# ProPrj_FOC_-L6234_2025-07-28.net
KiCad netlist of a schematic drawn in EasyEDA Pro
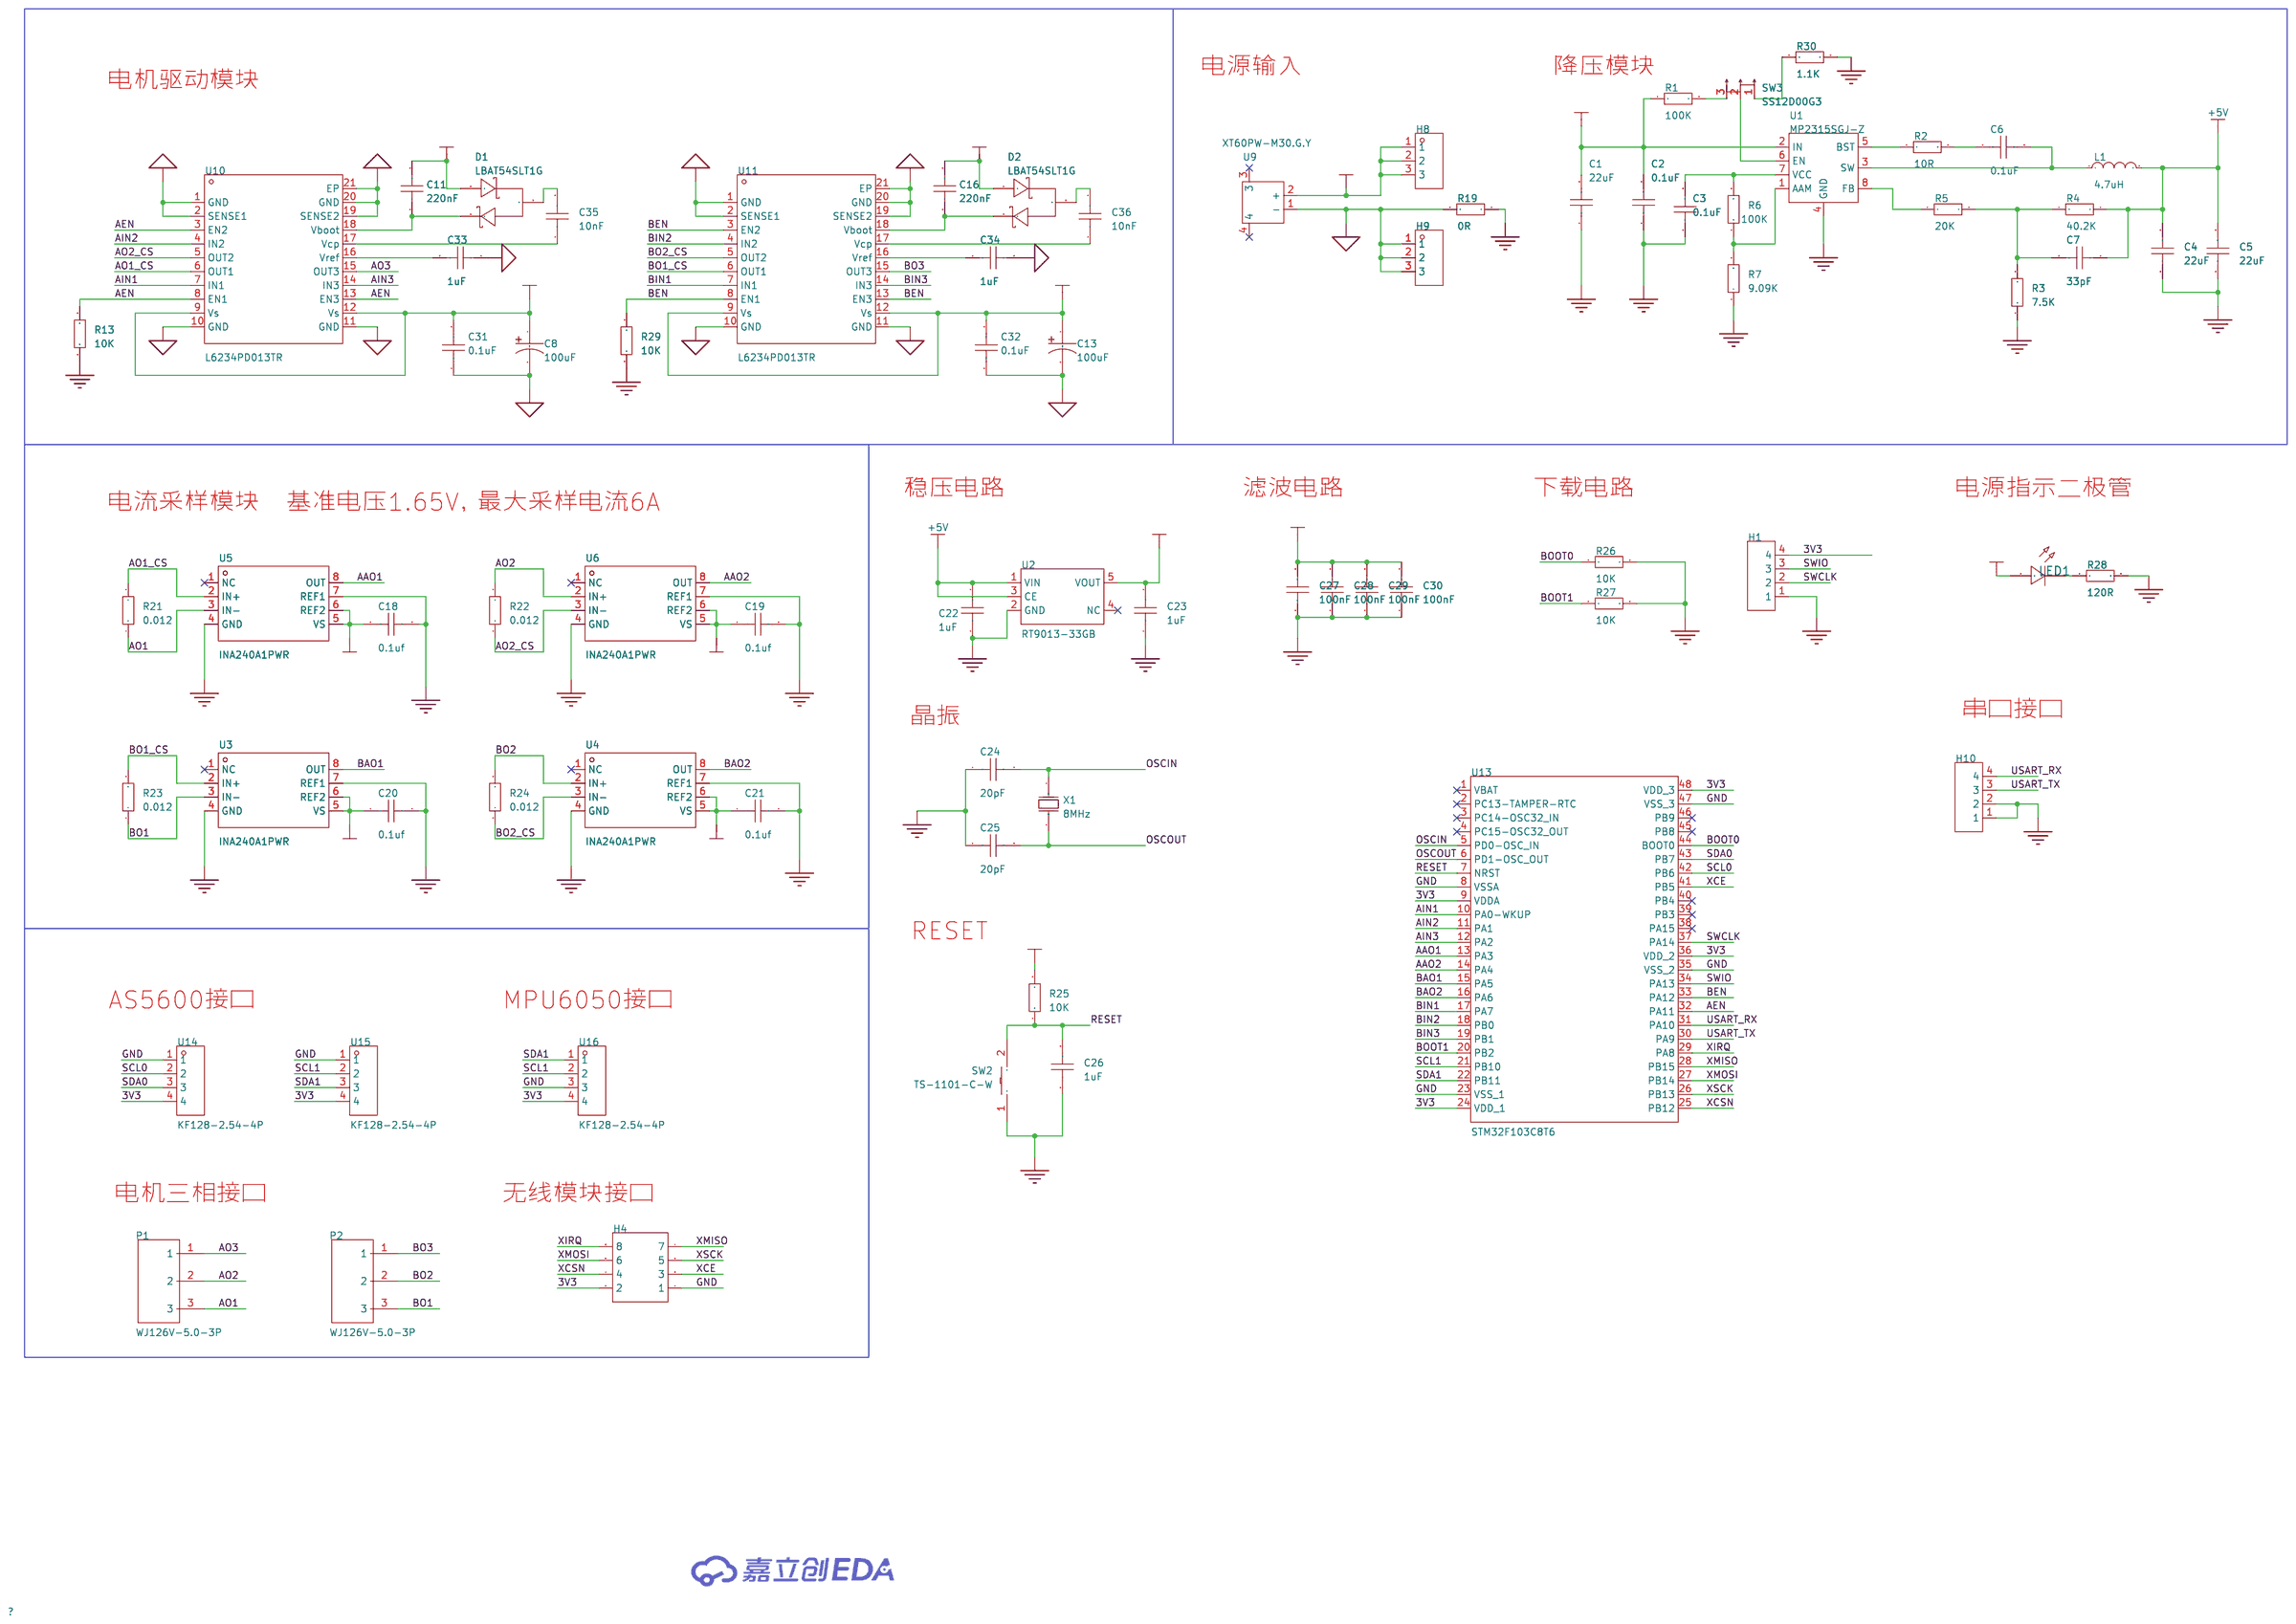
[diagram p0: schematic sheet]

(export (version "E")
  (design (tool "Eeschema 10.0.6"))
  (components
    (comp (ref "C1")
      (value "22uF")
      (footprint "easyedapro:C0603")
      (fields
        (field (name "Manufacturer Part") "CGA1206X5R226M350NT")
        (field (name "Manufacturer") "HRE(芯声)")
      )
      (libsource (lib "easyedapro") (part "CapAcitance"))
    )
    (comp (ref "C2")
      (value "0.1uF")
      (footprint "easyedapro:C0603")
      (libsource (lib "easyedapro") (part "CapAcitance"))
    )
    (comp (ref "C3")
      (value "0.1uF")
      (footprint "easyedapro:C0603")
      (libsource (lib "easyedapro") (part "CapAcitance"))
    )
    (comp (ref "C4")
      (value "22uF")
      (footprint "easyedapro:C0603")
      (fields
        (field (name "Manufacturer Part") "CGA0805X5R226M350MT")
        (field (name "Manufacturer") "HRE(芯声)")
      )
      (libsource (lib "easyedapro") (part "CapAcitance"))
    )
    (comp (ref "C5")
      (value "22uF")
      (footprint "easyedapro:C0603")
      (fields
        (field (name "Manufacturer Part") "CGA0805X5R226M350MT")
        (field (name "Manufacturer") "HRE(芯声)")
      )
      (libsource (lib "easyedapro") (part "CapAcitance"))
    )
    (comp (ref "C6")
      (value "0.1uF")
      (footprint "easyedapro:C0603")
      (libsource (lib "easyedapro") (part "CapAcitance"))
    )
    (comp (ref "C7")
      (value "33pF")
      (footprint "easyedapro:C0603")
      (libsource (lib "easyedapro") (part "CapAcitance"))
    )
    (comp (ref "C8")
      (value "100uF")
      (footprint "easyedapro:CAP-SMD_BD6.3-L6.6-W6.6-FD")
      (description "容值:100uF;精度:±20%;额定电压:35V;纹波电流:-;等效串联电阻:-;")
      (fields (field (name "Manufacturer Part") "RVE1V101M0607") (field (name "Manufacturer") "HONOR(荣誉)"))
      (libsource (lib "easyedapro") (part "RVE1V101M0607"))
    )
    (comp (ref "C11")
      (value "220nF")
      (footprint "easyedapro:C0603")
      (libsource (lib "easyedapro") (part "CapAcitance"))
    )
    (comp (ref "C13")
      (value "100uF")
      (footprint "easyedapro:CAP-SMD_BD6.3-L6.6-W6.6-FD")
      (description "容值:100uF;精度:±20%;额定电压:35V;纹波电流:-;等效串联电阻:-;")
      (fields (field (name "Manufacturer Part") "RVE1V101M0607") (field (name "Manufacturer") "HONOR(荣誉)"))
      (libsource (lib "easyedapro") (part "RVE1V101M0607"))
    )
    (comp (ref "C16")
      (value "220nF")
      (footprint "easyedapro:C0603")
      (libsource (lib "easyedapro") (part "CapAcitance"))
    )
    (comp (ref "C18")
      (value "0.1uf")
      (footprint "easyedapro:C0603")
      (libsource (lib "easyedapro") (part "CapAcitance"))
    )
    (comp (ref "C19")
      (value "0.1uf")
      (footprint "easyedapro:C0603")
      (libsource (lib "easyedapro") (part "CapAcitance"))
    )
    (comp (ref "C20")
      (value "0.1uf")
      (footprint "easyedapro:C0603")
      (libsource (lib "easyedapro") (part "CapAcitance"))
    )
    (comp (ref "C21")
      (value "0.1uf")
      (footprint "easyedapro:C0603")
      (libsource (lib "easyedapro") (part "CapAcitance"))
    )
    (comp (ref "C22")
      (value "1uF")
      (footprint "easyedapro:C0603")
      (libsource (lib "easyedapro") (part "CapAcitance"))
    )
    (comp (ref "C23")
      (value "1uF")
      (footprint "easyedapro:C0603")
      (libsource (lib "easyedapro") (part "CapAcitance"))
    )
    (comp (ref "C24")
      (value "20pF")
      (footprint "easyedapro:C0603")
      (libsource (lib "easyedapro") (part "CapAcitance"))
    )
    (comp (ref "C25")
      (value "20pF")
      (footprint "easyedapro:C0603")
      (libsource (lib "easyedapro") (part "CapAcitance"))
    )
    (comp (ref "C26")
      (value "1uF")
      (footprint "easyedapro:C0603")
      (libsource (lib "easyedapro") (part "CapAcitance"))
    )
    (comp (ref "C27")
      (value "100nF")
      (footprint "easyedapro:C0603")
      (libsource (lib "easyedapro") (part "CapAcitance"))
    )
    (comp (ref "C28")
      (value "100nF")
      (footprint "easyedapro:C0603")
      (libsource (lib "easyedapro") (part "CapAcitance"))
    )
    (comp (ref "C29")
      (value "100nF")
      (footprint "easyedapro:C0603")
      (libsource (lib "easyedapro") (part "CapAcitance"))
    )
    (comp (ref "C30")
      (value "100nF")
      (footprint "easyedapro:C0603")
      (libsource (lib "easyedapro") (part "CapAcitance"))
    )
    (comp (ref "C31")
      (value "0.1uF")
      (footprint "easyedapro:C0603")
      (libsource (lib "easyedapro") (part "CapAcitance"))
    )
    (comp (ref "C32")
      (value "0.1uF")
      (footprint "easyedapro:C0603")
      (libsource (lib "easyedapro") (part "CapAcitance"))
    )
    (comp (ref "C33")
      (value "1uF")
      (footprint "easyedapro:C0603")
      (libsource (lib "easyedapro") (part "CapAcitance"))
    )
    (comp (ref "C34")
      (value "1uF")
      (footprint "easyedapro:C0603")
      (libsource (lib "easyedapro") (part "CapAcitance"))
    )
    (comp (ref "C35")
      (value "10nF")
      (footprint "easyedapro:C0603")
      (libsource (lib "easyedapro") (part "CapAcitance"))
    )
    (comp (ref "C36")
      (value "10nF")
      (footprint "easyedapro:C0603")
      (libsource (lib "easyedapro") (part "CapAcitance"))
    )
    (comp (ref "D1")
      (value "LBAT54SLT1G")
      (footprint "easyedapro:SOT-23_L2.9-W1.3-P1.90-LS2.4-BR")
      (description "正向压降(Vf):400mV;直流反向耐压(Vr):30V;整流电流:200mA;")
      (fields (field (name "Manufacturer") "LRC(乐山无线电)"))
      (libsource (lib "easyedapro") (part "LBAT54SLT1G"))
    )
    (comp (ref "D2")
      (value "LBAT54SLT1G")
      (footprint "easyedapro:SOT-23_L2.9-W1.3-P1.90-LS2.4-BR")
      (description "正向压降(Vf):400mV;直流反向耐压(Vr):30V;整流电流:200mA;")
      (fields (field (name "Manufacturer") "LRC(乐山无线电)"))
      (libsource (lib "easyedapro") (part "LBAT54SLT1G"))
    )
    (comp (ref "H1")
      (value "~")
      (footprint "easyedapro:HDR-TH_4P-P2.54-V-M")
      (libsource (lib "easyedapro") (part "PZ254V-11-04P"))
    )
    (comp (ref "H4")
      (value "~")
      (footprint "easyedapro:HDR-TH_8P-P2.54-V-F-R2-C4-S2.54-1")
      (libsource (lib "easyedapro") (part "HDR-F-2.54_2x4"))
    )
    (comp (ref "H8")
      (value "~")
      (footprint "easyedapro:HDR-TH_3P-P2.54-V-M")
      (libsource (lib "easyedapro") (part "PZ254V-11-03P_C2937625"))
    )
    (comp (ref "H9")
      (value "~")
      (footprint "easyedapro:HDR-TH_3P-P2.54-V-M")
      (libsource (lib "easyedapro") (part "PZ254V-11-03P_C2937625"))
    )
    (comp (ref "H10")
      (value "~")
      (footprint "easyedapro:HDR-TH_4P-P2.54-V-M")
      (libsource (lib "easyedapro") (part "PZ254V-11-04P"))
    )
    (comp (ref "L1")
      (value "4.7uH")
      (footprint "easyedapro:IND-SMD_L7.3-W6.6")
      (description "电感值:4.7uH;精度:±20%;额定电流:5.5A;饱和电流(Isat):7A;")
      (fields (field (name "Manufacturer Part") "MCS0630-4R7MPY1") (field (name "Manufacturer") "PSA(信昌电陶)"))
      (libsource (lib "easyedapro") (part "MCS0630-4R7MPY1"))
    )
    (comp (ref "LED1")
      (value "~")
      (footprint "easyedapro:LED_0603")
      (libsource (lib "easyedapro") (part "LED_R"))
    )
    (comp (ref "P1")
      (value "WJ126V-5.0-3P")
      (footprint "easyedapro:CONN-TH_3P-P5.00_WJ126V-5.0-3P")
      (fields (field (name "Manufacturer") "KANGNEX(康奈克斯电气)"))
      (libsource (lib "easyedapro") (part "WJ126V-5.0-3P"))
    )
    (comp (ref "P2")
      (value "WJ126V-5.0-3P")
      (footprint "easyedapro:CONN-TH_3P-P5.00_WJ126V-5.0-3P")
      (fields (field (name "Manufacturer") "KANGNEX(康奈克斯电气)"))
      (libsource (lib "easyedapro") (part "WJ126V-5.0-3P"))
    )
    (comp (ref "R1") (value "100K") (footprint "easyedapro:R0805") (libsource (lib "easyedapro") (part "电阻")))
    (comp (ref "R2") (value "10R") (footprint "easyedapro:R0805") (libsource (lib "easyedapro") (part "电阻")))
    (comp (ref "R3") (value "7.5K") (footprint "easyedapro:R0805") (libsource (lib "easyedapro") (part "电阻")))
    (comp (ref "R4")
      (value "40.2K")
      (footprint "easyedapro:R0805")
      (libsource (lib "easyedapro") (part "电阻"))
    )
    (comp (ref "R5") (value "20K") (footprint "easyedapro:R0805") (libsource (lib "easyedapro") (part "电阻")))
    (comp (ref "R6") (value "100K") (footprint "easyedapro:R0805") (libsource (lib "easyedapro") (part "电阻")))
    (comp (ref "R7")
      (value "9.09K")
      (footprint "easyedapro:R0805")
      (libsource (lib "easyedapro") (part "电阻"))
    )
    (comp (ref "R13") (value "10K") (footprint "easyedapro:R0805") (libsource (lib "easyedapro") (part "电阻")))
    (comp (ref "R19") (value "0R") (footprint "easyedapro:R0805") (libsource (lib "easyedapro") (part "电阻")))
    (comp (ref "R21")
      (value "0.012")
      (footprint "easyedapro:R0805")
      (libsource (lib "easyedapro") (part "电阻"))
    )
    (comp (ref "R22")
      (value "0.012")
      (footprint "easyedapro:R0805")
      (libsource (lib "easyedapro") (part "电阻"))
    )
    (comp (ref "R23")
      (value "0.012")
      (footprint "easyedapro:R0805")
      (libsource (lib "easyedapro") (part "电阻"))
    )
    (comp (ref "R24")
      (value "0.012")
      (footprint "easyedapro:R0805")
      (libsource (lib "easyedapro") (part "电阻"))
    )
    (comp (ref "R25") (value "10K") (footprint "easyedapro:R0805") (libsource (lib "easyedapro") (part "电阻")))
    (comp (ref "R26") (value "10K") (footprint "easyedapro:R0805") (libsource (lib "easyedapro") (part "电阻")))
    (comp (ref "R27") (value "10K") (footprint "easyedapro:R0805") (libsource (lib "easyedapro") (part "电阻")))
    (comp (ref "R28")
      (value "120R")
      (footprint "easyedapro:R0805")
      (libsource (lib "easyedapro") (part "电阻"))
    )
    (comp (ref "R29") (value "10K") (footprint "easyedapro:R0805") (libsource (lib "easyedapro") (part "电阻")))
    (comp (ref "R30")
      (value "1.1K")
      (footprint "easyedapro:R0805")
      (libsource (lib "easyedapro") (part "电阻"))
    )
    (comp (ref "SW2")
      (value "TS-1101-C-W")
      (footprint "easyedapro:SW-SMD_L6.0-W3.3-LS8.0")
      (fields (field (name "Manufacturer") "XKB Connectivity(中国星坤)"))
      (libsource (lib "easyedapro") (part "TS-1101-C-W"))
    )
    (comp (ref "SW3")
      (value "SS12D00G3")
      (footprint "easyedapro:SW-TH_SS-12D01-GX")
      (libsource (lib "easyedapro") (part "SS12D00G3"))
    )
    (comp (ref "U1")
      (value "MP2315SGJ-Z")
      (footprint "easyedapro:TSOT-23-8_L2.9-W1.6-P0.65-LS2.8-BL")
      (description "功能类型:降压型;输出类型:固定;工作电压:4.5V~24V;输出电压:800mV~22.8V;输出电流:3A;")
      (fields (field (name "Manufacturer") "MPS(芯源)"))
      (libsource (lib "easyedapro") (part "MP2315SGJ-Z"))
    )
    (comp (ref "U2")
      (value "RT9013-33GB")
      (footprint "easyedapro:SOT-23-5_L2.9-W1.6-P0.95-LS2.8-BR")
      (description "输出类型:固定;工作电压:7V;输出电压:3.3V;输出电流:500mA;电源纹波抑制比(PSRR):-;输出极性:正极;")
      (fields (field (name "Manufacturer") "TECH PUBLIC(台舟)"))
      (libsource (lib "easyedapro") (part "RT9013-33GB_C19268157"))
    )
    (comp (ref "U3")
      (value "INA240A1PWR")
      (footprint "easyedapro:TSSOP-8_L4.4-W3.0-P0.65-LS6.4-BL")
      (description "放大器数:单路;")
      (fields (field (name "Manufacturer") "TI(德州仪器)"))
      (libsource (lib "easyedapro") (part "INA240A2PWR"))
    )
    (comp (ref "U4")
      (value "INA240A1PWR")
      (footprint "easyedapro:TSSOP-8_L4.4-W3.0-P0.65-LS6.4-BL")
      (description "放大器数:单路;")
      (fields (field (name "Manufacturer") "TI(德州仪器)"))
      (libsource (lib "easyedapro") (part "INA240A2PWR"))
    )
    (comp (ref "U5")
      (value "INA240A1PWR")
      (footprint "easyedapro:TSSOP-8_L4.4-W3.0-P0.65-LS6.4-BL")
      (description "放大器数:单路;")
      (fields (field (name "Manufacturer") "TI(德州仪器)"))
      (libsource (lib "easyedapro") (part "INA240A2PWR"))
    )
    (comp (ref "U6")
      (value "INA240A1PWR")
      (footprint "easyedapro:TSSOP-8_L4.4-W3.0-P0.65-LS6.4-BL")
      (description "放大器数:单路;")
      (fields (field (name "Manufacturer") "TI(德州仪器)"))
      (libsource (lib "easyedapro") (part "INA240A2PWR"))
    )
    (comp (ref "U9")
      (value "XT60PW-M30.G.Y")
      (footprint "easyedapro:CONN-TH_XT60PW-M")
      (libsource (lib "easyedapro") (part "XT60PW-M30.G.Y"))
    )
    (comp (ref "U10")
      (value "L6234PD013TR")
      (footprint "easyedapro:POWERSO20_L15.9-W11.0-P1.27-LS14.2-BL-EP")
      (description "三相电机驱动器")
      (fields (field (name "Manufacturer") "ST(意法半导体)"))
      (libsource (lib "easyedapro") (part "L6234PD013TR"))
    )
    (comp (ref "U11")
      (value "L6234PD013TR")
      (footprint "easyedapro:POWERSO20_L15.9-W11.0-P1.27-LS14.2-BL-EP")
      (description "三相电机驱动器")
      (fields (field (name "Manufacturer") "ST(意法半导体)"))
      (libsource (lib "easyedapro") (part "L6234PD013TR"))
    )
    (comp (ref "U13")
      (value "STM32F103C8T6")
      (footprint "easyedapro:LQFP-48_L7.0-W7.0-P0.50-LS9.0-BL")
      (description "CPU内核:ARM-M3;CPU最大主频:72MHz;应用领域:-;")
      (fields (field (name "Manufacturer") "ST(意法半导体)"))
      (libsource (lib "easyedapro") (part "STM32F103C8T6"))
    )
    (comp (ref "U14")
      (value "KF128-2.54-4P")
      (footprint "easyedapro:CONN-TH_4P-P2.54_KF128-2.54-4P")
      (fields (field (name "Manufacturer") "KEFA(科发)"))
      (libsource (lib "easyedapro") (part "KF128-2.54-4P"))
    )
    (comp (ref "U15")
      (value "KF128-2.54-4P")
      (footprint "easyedapro:CONN-TH_4P-P2.54_KF128-2.54-4P")
      (fields (field (name "Manufacturer") "KEFA(科发)"))
      (libsource (lib "easyedapro") (part "KF128-2.54-4P"))
    )
    (comp (ref "U16")
      (value "KF128-2.54-4P")
      (footprint "easyedapro:CONN-TH_4P-P2.54_KF128-2.54-4P")
      (fields (field (name "Manufacturer") "KEFA(科发)"))
      (libsource (lib "easyedapro") (part "KF128-2.54-4P"))
    )
    (comp (ref "X1")
      (value "8MHz")
      (fields (field (name "Manufacturer Part") "X49SD8MSD2SC") (field (name "Manufacturer") "YXC(扬兴晶振)"))
      (libsource (lib "easyedapro") (part "X49SM8MSD2SC"))
    )
  )
  (nets
    (net (code "1") (name "+5V") (class "Default")
      (node (ref "C22") (pin "2") (pinfunction "2_2") (pintype "input"))
      (node (ref "C4") (pin "2") (pinfunction "2_2") (pintype "input"))
      (node (ref "C5") (pin "2") (pinfunction "2_2") (pintype "input"))
      (node (ref "C7") (pin "2") (pinfunction "2_2") (pintype "input"))
      (node (ref "L1") (pin "2") (pinfunction "2_2") (pintype "unspecified"))
      (node (ref "R4") (pin "2") (pinfunction "2_2") (pintype "input"))
      (node (ref "U2") (pin "1") (pinfunction "VIN_1") (pintype "unspecified"))
      (node (ref "U2") (pin "3") (pinfunction "CE_3") (pintype "unspecified"))
    )
    (net (code "2") (name "/AAO1") (class "Default")
      (node (ref "U13") (pin "13") (pinfunction "PA3_13") (pintype "unspecified"))
      (node (ref "U5") (pin "8") (pinfunction "OUT_8") (pintype "unspecified"))
    )
    (net (code "3") (name "/AAO2") (class "Default")
      (node (ref "U13") (pin "14") (pinfunction "PA4_14") (pintype "unspecified"))
      (node (ref "U6") (pin "8") (pinfunction "OUT_8") (pintype "unspecified"))
    )
    (net (code "4") (name "/AEN") (class "Default")
      (node (ref "R13") (pin "2") (pinfunction "2_2") (pintype "input"))
      (node (ref "U10") (pin "13") (pinfunction "EN3_13") (pintype "unspecified"))
      (node (ref "U10") (pin "3") (pinfunction "EN2_3") (pintype "unspecified"))
      (node (ref "U10") (pin "8") (pinfunction "EN1_8") (pintype "unspecified"))
      (node (ref "U13") (pin "32") (pinfunction "PA11_32") (pintype "unspecified"))
    )
    (net (code "5") (name "/AIN1") (class "Default")
      (node (ref "U10") (pin "7") (pinfunction "IN1_7") (pintype "unspecified"))
      (node (ref "U13") (pin "10") (pinfunction "PA0-WKUP_10") (pintype "unspecified"))
    )
    (net (code "6") (name "/AIN2") (class "Default")
      (node (ref "U10") (pin "4") (pinfunction "IN2_4") (pintype "unspecified"))
      (node (ref "U13") (pin "11") (pinfunction "PA1_11") (pintype "unspecified"))
    )
    (net (code "7") (name "/AIN3") (class "Default")
      (node (ref "U10") (pin "14") (pinfunction "IN3_14") (pintype "unspecified"))
      (node (ref "U13") (pin "12") (pinfunction "PA2_12") (pintype "unspecified"))
    )
    (net (code "8") (name "/AO1") (class "Default")
      (node (ref "P1") (pin "3") (pinfunction "3_3") (pintype "input"))
      (node (ref "R21") (pin "1") (pinfunction "1_1") (pintype "input"))
      (node (ref "U5") (pin "3") (pinfunction "IN-_3") (pintype "unspecified"))
    )
    (net (code "9") (name "/AO1_CS") (class "Default")
      (node (ref "R21") (pin "2") (pinfunction "2_2") (pintype "input"))
      (node (ref "U10") (pin "6") (pinfunction "OUT1_6") (pintype "unspecified"))
      (node (ref "U5") (pin "2") (pinfunction "IN+_2") (pintype "unspecified"))
    )
    (net (code "10") (name "/AO2") (class "Default")
      (node (ref "P1") (pin "2") (pinfunction "2_2") (pintype "input"))
      (node (ref "R22") (pin "2") (pinfunction "2_2") (pintype "input"))
      (node (ref "U6") (pin "2") (pinfunction "IN+_2") (pintype "unspecified"))
    )
    (net (code "11") (name "/AO2_CS") (class "Default")
      (node (ref "R22") (pin "1") (pinfunction "1_1") (pintype "input"))
      (node (ref "U10") (pin "5") (pinfunction "OUT2_5") (pintype "unspecified"))
      (node (ref "U6") (pin "3") (pinfunction "IN-_3") (pintype "unspecified"))
    )
    (net (code "12") (name "/AO3") (class "Default")
      (node (ref "P1") (pin "1") (pinfunction "1_1") (pintype "input"))
      (node (ref "U10") (pin "15") (pinfunction "OUT3_15") (pintype "unspecified"))
    )
    (net (code "13") (name "/BAO1") (class "Default")
      (node (ref "U13") (pin "15") (pinfunction "PA5_15") (pintype "unspecified"))
      (node (ref "U3") (pin "8") (pinfunction "OUT_8") (pintype "unspecified"))
    )
    (net (code "14") (name "/BAO2") (class "Default")
      (node (ref "U13") (pin "16") (pinfunction "PA6_16") (pintype "unspecified"))
      (node (ref "U4") (pin "8") (pinfunction "OUT_8") (pintype "unspecified"))
    )
    (net (code "15") (name "/BEN") (class "Default")
      (node (ref "R29") (pin "2") (pinfunction "2_2") (pintype "input"))
      (node (ref "U11") (pin "13") (pinfunction "EN3_13") (pintype "unspecified"))
      (node (ref "U11") (pin "3") (pinfunction "EN2_3") (pintype "unspecified"))
      (node (ref "U11") (pin "8") (pinfunction "EN1_8") (pintype "unspecified"))
      (node (ref "U13") (pin "33") (pinfunction "PA12_33") (pintype "unspecified"))
    )
    (net (code "16") (name "/BIN1") (class "Default")
      (node (ref "U11") (pin "7") (pinfunction "IN1_7") (pintype "unspecified"))
      (node (ref "U13") (pin "17") (pinfunction "PA7_17") (pintype "unspecified"))
    )
    (net (code "17") (name "/BIN2") (class "Default")
      (node (ref "U11") (pin "4") (pinfunction "IN2_4") (pintype "unspecified"))
      (node (ref "U13") (pin "18") (pinfunction "PB0_18") (pintype "unspecified"))
    )
    (net (code "18") (name "/BIN3") (class "Default")
      (node (ref "U11") (pin "14") (pinfunction "IN3_14") (pintype "unspecified"))
      (node (ref "U13") (pin "19") (pinfunction "PB1_19") (pintype "unspecified"))
    )
    (net (code "19") (name "/BO1") (class "Default")
      (node (ref "P2") (pin "3") (pinfunction "3_3") (pintype "input"))
      (node (ref "R23") (pin "1") (pinfunction "1_1") (pintype "input"))
      (node (ref "U3") (pin "3") (pinfunction "IN-_3") (pintype "unspecified"))
    )
    (net (code "20") (name "/BO1_CS") (class "Default")
      (node (ref "R23") (pin "2") (pinfunction "2_2") (pintype "input"))
      (node (ref "U11") (pin "6") (pinfunction "OUT1_6") (pintype "unspecified"))
      (node (ref "U3") (pin "2") (pinfunction "IN+_2") (pintype "unspecified"))
    )
    (net (code "21") (name "/BO2") (class "Default")
      (node (ref "P2") (pin "2") (pinfunction "2_2") (pintype "input"))
      (node (ref "R24") (pin "2") (pinfunction "2_2") (pintype "input"))
      (node (ref "U4") (pin "2") (pinfunction "IN+_2") (pintype "unspecified"))
    )
    (net (code "22") (name "/BO2_CS") (class "Default")
      (node (ref "R24") (pin "1") (pinfunction "1_1") (pintype "input"))
      (node (ref "U11") (pin "5") (pinfunction "OUT2_5") (pintype "unspecified"))
      (node (ref "U4") (pin "3") (pinfunction "IN-_3") (pintype "unspecified"))
    )
    (net (code "23") (name "/BO3") (class "Default")
      (node (ref "P2") (pin "1") (pinfunction "1_1") (pintype "input"))
      (node (ref "U11") (pin "15") (pinfunction "OUT3_15") (pintype "unspecified"))
    )
    (net (code "24") (name "/BOOT0") (class "Default")
      (node (ref "R26") (pin "1") (pinfunction "1_1") (pintype "input"))
      (node (ref "U13") (pin "44") (pinfunction "BOOT0_44") (pintype "unspecified"))
    )
    (net (code "25") (name "/BOOT1") (class "Default")
      (node (ref "R27") (pin "1") (pinfunction "1_1") (pintype "input"))
      (node (ref "U13") (pin "20") (pinfunction "PB2_20") (pintype "unspecified"))
    )
    (net (code "26") (name "/OSCIN") (class "Default")
      (node (ref "C24") (pin "2") (pinfunction "2_2") (pintype "input"))
      (node (ref "U13") (pin "5") (pinfunction "PD0-OSC_IN_5") (pintype "unspecified"))
      (node (ref "X1") (pin "1") (pinfunction "OSC1_1") (pintype "input"))
    )
    (net (code "27") (name "/OSCOUT") (class "Default")
      (node (ref "C25") (pin "2") (pinfunction "2_2") (pintype "input"))
      (node (ref "U13") (pin "6") (pinfunction "PD1-OSC_OUT_6") (pintype "unspecified"))
      (node (ref "X1") (pin "2") (pinfunction "OSC2_2") (pintype "input"))
    )
    (net (code "28") (name "/RESET") (class "Default")
      (node (ref "C26") (pin "2") (pinfunction "2_2") (pintype "input"))
      (node (ref "R25") (pin "1") (pinfunction "1_1") (pintype "input"))
      (node (ref "SW2") (pin "2") (pinfunction "2_2") (pintype "unspecified"))
      (node (ref "U13") (pin "7") (pinfunction "NRST_7") (pintype "unspecified"))
    )
    (net (code "29") (name "/SCL0") (class "Default")
      (node (ref "U13") (pin "42") (pinfunction "PB6_42") (pintype "unspecified"))
      (node (ref "U14") (pin "2") (pinfunction "2_2") (pintype "unspecified"))
    )
    (net (code "30") (name "/SCL1") (class "Default")
      (node (ref "U13") (pin "21") (pinfunction "PB10_21") (pintype "unspecified"))
      (node (ref "U15") (pin "2") (pinfunction "2_2") (pintype "unspecified"))
      (node (ref "U16") (pin "2") (pinfunction "2_2") (pintype "unspecified"))
    )
    (net (code "31") (name "/SDA0") (class "Default")
      (node (ref "U13") (pin "43") (pinfunction "PB7_43") (pintype "unspecified"))
      (node (ref "U14") (pin "3") (pinfunction "3_3") (pintype "unspecified"))
    )
    (net (code "32") (name "/SDA1") (class "Default")
      (node (ref "U13") (pin "22") (pinfunction "PB11_22") (pintype "unspecified"))
      (node (ref "U15") (pin "3") (pinfunction "3_3") (pintype "unspecified"))
      (node (ref "U16") (pin "1") (pinfunction "1_1") (pintype "unspecified"))
    )
    (net (code "33") (name "/SWCLK") (class "Default")
      (node (ref "H1") (pin "2") (pinfunction "2_2") (pintype "unspecified"))
      (node (ref "U13") (pin "37") (pinfunction "PA14_37") (pintype "unspecified"))
    )
    (net (code "34") (name "/SWIO") (class "Default")
      (node (ref "H1") (pin "3") (pinfunction "3_3") (pintype "unspecified"))
      (node (ref "U13") (pin "34") (pinfunction "PA13_34") (pintype "unspecified"))
    )
    (net (code "35") (name "/USART_RX") (class "Default")
      (node (ref "H10") (pin "4") (pinfunction "4_4") (pintype "unspecified"))
      (node (ref "U13") (pin "31") (pinfunction "PA10_31") (pintype "unspecified"))
    )
    (net (code "36") (name "/USART_TX") (class "Default")
      (node (ref "H10") (pin "3") (pinfunction "3_3") (pintype "unspecified"))
      (node (ref "U13") (pin "30") (pinfunction "PA9_30") (pintype "unspecified"))
    )
    (net (code "37") (name "/XCE") (class "Default")
      (node (ref "H4") (pin "3") (pinfunction "3_3") (pintype "input"))
      (node (ref "U13") (pin "41") (pinfunction "PB5_41") (pintype "unspecified"))
    )
    (net (code "38") (name "/XCSN") (class "Default")
      (node (ref "H4") (pin "4") (pinfunction "4_4") (pintype "input"))
      (node (ref "U13") (pin "25") (pinfunction "PB12_25") (pintype "unspecified"))
    )
    (net (code "39") (name "/XIRQ") (class "Default")
      (node (ref "H4") (pin "8") (pinfunction "8_8") (pintype "input"))
      (node (ref "U13") (pin "29") (pinfunction "PA8_29") (pintype "unspecified"))
    )
    (net (code "40") (name "/XMISO") (class "Default")
      (node (ref "H4") (pin "7") (pinfunction "7_7") (pintype "input"))
      (node (ref "U13") (pin "28") (pinfunction "PB15_28") (pintype "unspecified"))
    )
    (net (code "41") (name "/XMOSI") (class "Default")
      (node (ref "H4") (pin "6") (pinfunction "6_6") (pintype "input"))
      (node (ref "U13") (pin "27") (pinfunction "PB14_27") (pintype "unspecified"))
    )
    (net (code "42") (name "/XSCK") (class "Default")
      (node (ref "H4") (pin "5") (pinfunction "5_5") (pintype "input"))
      (node (ref "U13") (pin "26") (pinfunction "PB13_26") (pintype "unspecified"))
    )
    (net (code "43") (name "3V3") (class "Default")
      (node (ref "C18") (pin "1") (pinfunction "1_1") (pintype "input"))
      (node (ref "C19") (pin "1") (pinfunction "1_1") (pintype "input"))
      (node (ref "C20") (pin "1") (pinfunction "1_1") (pintype "input"))
      (node (ref "C21") (pin "1") (pinfunction "1_1") (pintype "input"))
      (node (ref "C23") (pin "2") (pinfunction "2_2") (pintype "input"))
      (node (ref "C27") (pin "2") (pinfunction "2_2") (pintype "input"))
      (node (ref "C28") (pin "2") (pinfunction "2_2") (pintype "input"))
      (node (ref "C29") (pin "2") (pinfunction "2_2") (pintype "input"))
      (node (ref "C30") (pin "2") (pinfunction "2_2") (pintype "input"))
      (node (ref "H1") (pin "4") (pinfunction "4_4") (pintype "unspecified"))
      (node (ref "H4") (pin "2") (pinfunction "2_2") (pintype "input"))
      (node (ref "LED1") (pin "2") (pinfunction "A_2") (pintype "input"))
      (node (ref "R25") (pin "2") (pinfunction "2_2") (pintype "input"))
      (node (ref "U13") (pin "24") (pinfunction "VDD_1_24") (pintype "unspecified"))
      (node (ref "U13") (pin "36") (pinfunction "VDD_2_36") (pintype "unspecified"))
      (node (ref "U13") (pin "48") (pinfunction "VDD_3_48") (pintype "unspecified"))
      (node (ref "U13") (pin "9") (pinfunction "VDDA_9") (pintype "unspecified"))
      (node (ref "U14") (pin "4") (pinfunction "4_4") (pintype "unspecified"))
      (node (ref "U15") (pin "4") (pinfunction "4_4") (pintype "unspecified"))
      (node (ref "U16") (pin "4") (pinfunction "4_4") (pintype "unspecified"))
      (node (ref "U2") (pin "5") (pinfunction "VOUT_5") (pintype "unspecified"))
      (node (ref "U3") (pin "5") (pinfunction "VS_5") (pintype "unspecified"))
      (node (ref "U3") (pin "6") (pinfunction "REF2_6") (pintype "unspecified"))
      (node (ref "U4") (pin "5") (pinfunction "VS_5") (pintype "unspecified"))
      (node (ref "U4") (pin "6") (pinfunction "REF2_6") (pintype "unspecified"))
      (node (ref "U5") (pin "5") (pinfunction "VS_5") (pintype "unspecified"))
      (node (ref "U5") (pin "6") (pinfunction "REF2_6") (pintype "unspecified"))
      (node (ref "U6") (pin "5") (pinfunction "VS_5") (pintype "unspecified"))
      (node (ref "U6") (pin "6") (pinfunction "REF2_6") (pintype "unspecified"))
    )
    (net (code "44") (name "AGND") (class "Default")
      (node (ref "C13") (pin "2") (pinfunction "2_2") (pintype "unspecified"))
      (node (ref "C31") (pin "1") (pinfunction "1_1") (pintype "input"))
      (node (ref "C32") (pin "1") (pinfunction "1_1") (pintype "input"))
      (node (ref "C33") (pin "1") (pinfunction "1_1") (pintype "input"))
      (node (ref "C34") (pin "1") (pinfunction "1_1") (pintype "input"))
      (node (ref "C8") (pin "2") (pinfunction "2_2") (pintype "unspecified"))
      (node (ref "H9") (pin "1") (pinfunction "1_1") (pintype "input"))
      (node (ref "H9") (pin "2") (pinfunction "2_2") (pintype "input"))
      (node (ref "H9") (pin "3") (pinfunction "3_3") (pintype "input"))
      (node (ref "R19") (pin "2") (pinfunction "2_2") (pintype "input"))
      (node (ref "U10") (pin "1") (pinfunction "GND_1") (pintype "unspecified"))
      (node (ref "U10") (pin "10") (pinfunction "GND_10") (pintype "unspecified"))
      (node (ref "U10") (pin "11") (pinfunction "GND_11") (pintype "unspecified"))
      (node (ref "U10") (pin "19") (pinfunction "SENSE2_19") (pintype "unspecified"))
      (node (ref "U10") (pin "2") (pinfunction "SENSE1_2") (pintype "unspecified"))
      (node (ref "U10") (pin "20") (pinfunction "GND_20") (pintype "unspecified"))
      (node (ref "U10") (pin "21") (pinfunction "EP_21") (pintype "unspecified"))
      (node (ref "U11") (pin "1") (pinfunction "GND_1") (pintype "unspecified"))
      (node (ref "U11") (pin "10") (pinfunction "GND_10") (pintype "unspecified"))
      (node (ref "U11") (pin "11") (pinfunction "GND_11") (pintype "unspecified"))
      (node (ref "U11") (pin "19") (pinfunction "SENSE2_19") (pintype "unspecified"))
      (node (ref "U11") (pin "2") (pinfunction "SENSE1_2") (pintype "unspecified"))
      (node (ref "U11") (pin "20") (pinfunction "GND_20") (pintype "unspecified"))
      (node (ref "U11") (pin "21") (pinfunction "EP_21") (pintype "unspecified"))
      (node (ref "U9") (pin "1") (pinfunction "-_1") (pintype "unspecified"))
    )
    (net (code "45") (name "GND") (class "Default")
      (node (ref "C1") (pin "1") (pinfunction "1_1") (pintype "input"))
      (node (ref "C18") (pin "2") (pinfunction "2_2") (pintype "input"))
      (node (ref "C19") (pin "2") (pinfunction "2_2") (pintype "input"))
      (node (ref "C2") (pin "1") (pinfunction "1_1") (pintype "input"))
      (node (ref "C20") (pin "2") (pinfunction "2_2") (pintype "input"))
      (node (ref "C21") (pin "2") (pinfunction "2_2") (pintype "input"))
      (node (ref "C22") (pin "1") (pinfunction "1_1") (pintype "input"))
      (node (ref "C23") (pin "1") (pinfunction "1_1") (pintype "input"))
      (node (ref "C24") (pin "1") (pinfunction "1_1") (pintype "input"))
      (node (ref "C25") (pin "1") (pinfunction "1_1") (pintype "input"))
      (node (ref "C26") (pin "1") (pinfunction "1_1") (pintype "input"))
      (node (ref "C27") (pin "1") (pinfunction "1_1") (pintype "input"))
      (node (ref "C28") (pin "1") (pinfunction "1_1") (pintype "input"))
      (node (ref "C29") (pin "1") (pinfunction "1_1") (pintype "input"))
      (node (ref "C3") (pin "1") (pinfunction "1_1") (pintype "input"))
      (node (ref "C30") (pin "1") (pinfunction "1_1") (pintype "input"))
      (node (ref "C4") (pin "1") (pinfunction "1_1") (pintype "input"))
      (node (ref "C5") (pin "1") (pinfunction "1_1") (pintype "input"))
      (node (ref "H1") (pin "1") (pinfunction "1_1") (pintype "unspecified"))
      (node (ref "H10") (pin "1") (pinfunction "1_1") (pintype "unspecified"))
      (node (ref "H10") (pin "2") (pinfunction "2_2") (pintype "unspecified"))
      (node (ref "H4") (pin "1") (pinfunction "1_1") (pintype "input"))
      (node (ref "R13") (pin "1") (pinfunction "1_1") (pintype "input"))
      (node (ref "R19") (pin "1") (pinfunction "1_1") (pintype "input"))
      (node (ref "R26") (pin "2") (pinfunction "2_2") (pintype "input"))
      (node (ref "R27") (pin "2") (pinfunction "2_2") (pintype "input"))
      (node (ref "R28") (pin "2") (pinfunction "2_2") (pintype "input"))
      (node (ref "R29") (pin "1") (pinfunction "1_1") (pintype "input"))
      (node (ref "R3") (pin "1") (pinfunction "1_1") (pintype "input"))
      (node (ref "R30") (pin "2") (pinfunction "2_2") (pintype "input"))
      (node (ref "R7") (pin "1") (pinfunction "1_1") (pintype "input"))
      (node (ref "SW2") (pin "1") (pinfunction "1_1") (pintype "unspecified"))
      (node (ref "U1") (pin "4") (pinfunction "GND_4") (pintype "unspecified"))
      (node (ref "U13") (pin "23") (pinfunction "VSS_1_23") (pintype "unspecified"))
      (node (ref "U13") (pin "35") (pinfunction "VSS_2_35") (pintype "unspecified"))
      (node (ref "U13") (pin "47") (pinfunction "VSS_3_47") (pintype "unspecified"))
      (node (ref "U13") (pin "8") (pinfunction "VSSA_8") (pintype "unspecified"))
      (node (ref "U14") (pin "1") (pinfunction "1_1") (pintype "unspecified"))
      (node (ref "U15") (pin "1") (pinfunction "1_1") (pintype "unspecified"))
      (node (ref "U16") (pin "3") (pinfunction "3_3") (pintype "unspecified"))
      (node (ref "U2") (pin "2") (pinfunction "GND_2") (pintype "unspecified"))
      (node (ref "U3") (pin "4") (pinfunction "GND_4") (pintype "unspecified"))
      (node (ref "U3") (pin "7") (pinfunction "REF1_7") (pintype "unspecified"))
      (node (ref "U4") (pin "4") (pinfunction "GND_4") (pintype "unspecified"))
      (node (ref "U4") (pin "7") (pinfunction "REF1_7") (pintype "unspecified"))
      (node (ref "U5") (pin "4") (pinfunction "GND_4") (pintype "unspecified"))
      (node (ref "U5") (pin "7") (pinfunction "REF1_7") (pintype "unspecified"))
      (node (ref "U6") (pin "4") (pinfunction "GND_4") (pintype "unspecified"))
      (node (ref "U6") (pin "7") (pinfunction "REF1_7") (pintype "unspecified"))
    )
    (net (code "46") (name "Net-(C6-Pad1)") (class "Default")
      (node (ref "C6") (pin "1") (pinfunction "1_1") (pintype "input"))
      (node (ref "R2") (pin "2") (pinfunction "2_2") (pintype "input"))
    )
    (net (code "47") (name "Net-(C7-Pad1)") (class "Default")
      (node (ref "C7") (pin "1") (pinfunction "1_1") (pintype "input"))
      (node (ref "R3") (pin "2") (pinfunction "2_2") (pintype "input"))
      (node (ref "R4") (pin "1") (pinfunction "1_1") (pintype "input"))
      (node (ref "R5") (pin "2") (pinfunction "2_2") (pintype "input"))
    )
    (net (code "48") (name "Net-(D1-AK)") (class "Default")
      (node (ref "C35") (pin "2") (pinfunction "2_2") (pintype "input"))
      (node (ref "D1") (pin "3") (pinfunction "AK_3") (pintype "unspecified"))
    )
    (net (code "49") (name "Net-(D1-K)") (class "Default")
      (node (ref "C11") (pin "1") (pinfunction "1_1") (pintype "input"))
      (node (ref "D1") (pin "2") (pinfunction "K_2") (pintype "unspecified"))
      (node (ref "U10") (pin "18") (pinfunction "Vboot_18") (pintype "unspecified"))
    )
    (net (code "50") (name "Net-(D2-AK)") (class "Default")
      (node (ref "C36") (pin "2") (pinfunction "2_2") (pintype "input"))
      (node (ref "D2") (pin "3") (pinfunction "AK_3") (pintype "unspecified"))
    )
    (net (code "51") (name "Net-(D2-K)") (class "Default")
      (node (ref "C16") (pin "1") (pinfunction "1_1") (pintype "input"))
      (node (ref "D2") (pin "2") (pinfunction "K_2") (pintype "unspecified"))
      (node (ref "U11") (pin "18") (pinfunction "Vboot_18") (pintype "unspecified"))
    )
    (net (code "52") (name "Net-(LED1-C)") (class "Default")
      (node (ref "LED1") (pin "1") (pinfunction "C_1") (pintype "input"))
      (node (ref "R28") (pin "1") (pinfunction "1_1") (pintype "input"))
    )
    (net (code "53") (name "Net-(R1-Pad2)") (class "Default")
      (node (ref "R1") (pin "2") (pinfunction "2_2") (pintype "input"))
      (node (ref "SW3") (pin "3") (pinfunction "3_3") (pintype "unspecified"))
    )
    (net (code "54") (name "Net-(R30-Pad1)") (class "Default")
      (node (ref "R30") (pin "1") (pinfunction "1_1") (pintype "input"))
      (node (ref "SW3") (pin "1") (pinfunction "1_1") (pintype "unspecified"))
    )
    (net (code "55") (name "Net-(U1-AAM)") (class "Default")
      (node (ref "R6") (pin "1") (pinfunction "1_1") (pintype "input"))
      (node (ref "R7") (pin "2") (pinfunction "2_2") (pintype "input"))
      (node (ref "U1") (pin "1") (pinfunction "AAM_1") (pintype "unspecified"))
    )
    (net (code "56") (name "Net-(U1-BST)") (class "Default")
      (node (ref "R2") (pin "1") (pinfunction "1_1") (pintype "input"))
      (node (ref "U1") (pin "5") (pinfunction "BST_5") (pintype "unspecified"))
    )
    (net (code "57") (name "Net-(U1-EN)") (class "Default")
      (node (ref "SW3") (pin "2") (pinfunction "2_2") (pintype "unspecified"))
      (node (ref "U1") (pin "6") (pinfunction "EN_6") (pintype "unspecified"))
    )
    (net (code "58") (name "Net-(U1-FB)") (class "Default")
      (node (ref "R5") (pin "1") (pinfunction "1_1") (pintype "input"))
      (node (ref "U1") (pin "8") (pinfunction "FB_8") (pintype "unspecified"))
    )
    (net (code "59") (name "Net-(U1-SW)") (class "Default")
      (node (ref "C6") (pin "2") (pinfunction "2_2") (pintype "input"))
      (node (ref "L1") (pin "1") (pinfunction "1_1") (pintype "unspecified"))
      (node (ref "U1") (pin "3") (pinfunction "SW_3") (pintype "unspecified"))
    )
    (net (code "60") (name "Net-(U1-VCC)") (class "Default")
      (node (ref "C3") (pin "2") (pinfunction "2_2") (pintype "input"))
      (node (ref "R6") (pin "2") (pinfunction "2_2") (pintype "input"))
      (node (ref "U1") (pin "7") (pinfunction "VCC_7") (pintype "unspecified"))
    )
    (net (code "61") (name "Net-(U10-Vcp)") (class "Default")
      (node (ref "C35") (pin "1") (pinfunction "1_1") (pintype "input"))
      (node (ref "U10") (pin "17") (pinfunction "Vcp_17") (pintype "unspecified"))
    )
    (net (code "62") (name "Net-(U10-Vref)") (class "Default")
      (node (ref "C33") (pin "2") (pinfunction "2_2") (pintype "input"))
      (node (ref "U10") (pin "16") (pinfunction "Vref_16") (pintype "unspecified"))
    )
    (net (code "63") (name "Net-(U11-Vcp)") (class "Default")
      (node (ref "C36") (pin "1") (pinfunction "1_1") (pintype "input"))
      (node (ref "U11") (pin "17") (pinfunction "Vcp_17") (pintype "unspecified"))
    )
    (net (code "64") (name "Net-(U11-Vref)") (class "Default")
      (node (ref "C34") (pin "2") (pinfunction "2_2") (pintype "input"))
      (node (ref "U11") (pin "16") (pinfunction "Vref_16") (pintype "unspecified"))
    )
    (net (code "65") (name "VIN") (class "Default")
      (node (ref "C1") (pin "2") (pinfunction "2_2") (pintype "input"))
      (node (ref "C11") (pin "2") (pinfunction "2_2") (pintype "input"))
      (node (ref "C13") (pin "1") (pinfunction "1_1") (pintype "unspecified"))
      (node (ref "C16") (pin "2") (pinfunction "2_2") (pintype "input"))
      (node (ref "C2") (pin "2") (pinfunction "2_2") (pintype "input"))
      (node (ref "C31") (pin "2") (pinfunction "2_2") (pintype "input"))
      (node (ref "C32") (pin "2") (pinfunction "2_2") (pintype "input"))
      (node (ref "C8") (pin "1") (pinfunction "1_1") (pintype "unspecified"))
      (node (ref "D1") (pin "1") (pinfunction "A_1") (pintype "unspecified"))
      (node (ref "D2") (pin "1") (pinfunction "A_1") (pintype "unspecified"))
      (node (ref "H8") (pin "1") (pinfunction "1_1") (pintype "input"))
      (node (ref "H8") (pin "2") (pinfunction "2_2") (pintype "input"))
      (node (ref "H8") (pin "3") (pinfunction "3_3") (pintype "input"))
      (node (ref "R1") (pin "1") (pinfunction "1_1") (pintype "input"))
      (node (ref "U1") (pin "2") (pinfunction "IN_2") (pintype "unspecified"))
      (node (ref "U10") (pin "12") (pinfunction "Vs_12") (pintype "unspecified"))
      (node (ref "U10") (pin "9") (pinfunction "Vs_9") (pintype "unspecified"))
      (node (ref "U11") (pin "12") (pinfunction "Vs_12") (pintype "unspecified"))
      (node (ref "U11") (pin "9") (pinfunction "Vs_9") (pintype "unspecified"))
      (node (ref "U9") (pin "2") (pinfunction "+_2") (pintype "unspecified"))
    )
    (net (code "66") (name "unconnected-(U2-NC-Pad4)") (class "Default")
      (node (ref "U2") (pin "4") (pinfunction "NC_4") (pintype "unspecified+no_connect"))
    )
    (net (code "67") (name "unconnected-(U3-NC-Pad1)") (class "Default")
      (node (ref "U3") (pin "1") (pinfunction "NC_1") (pintype "unspecified+no_connect"))
    )
    (net (code "68") (name "unconnected-(U4-NC-Pad1)") (class "Default")
      (node (ref "U4") (pin "1") (pinfunction "NC_1") (pintype "unspecified+no_connect"))
    )
    (net (code "69") (name "unconnected-(U5-NC-Pad1)") (class "Default")
      (node (ref "U5") (pin "1") (pinfunction "NC_1") (pintype "unspecified+no_connect"))
    )
    (net (code "70") (name "unconnected-(U6-NC-Pad1)") (class "Default")
      (node (ref "U6") (pin "1") (pinfunction "NC_1") (pintype "unspecified+no_connect"))
    )
    (net (code "71") (name "unconnected-(U9-Pad3)") (class "Default")
      (node (ref "U9") (pin "3") (pinfunction "3_3") (pintype "unspecified+no_connect"))
    )
    (net (code "72") (name "unconnected-(U9-Pad4)") (class "Default")
      (node (ref "U9") (pin "4") (pinfunction "4_4") (pintype "unspecified+no_connect"))
    )
    (net (code "73") (name "unconnected-(U13-PA15-Pad38)") (class "Default")
      (node (ref "U13") (pin "38") (pinfunction "PA15_38") (pintype "unspecified+no_connect"))
    )
    (net (code "74") (name "unconnected-(U13-PB3-Pad39)") (class "Default")
      (node (ref "U13") (pin "39") (pinfunction "PB3_39") (pintype "unspecified+no_connect"))
    )
    (net (code "75") (name "unconnected-(U13-PB4-Pad40)") (class "Default")
      (node (ref "U13") (pin "40") (pinfunction "PB4_40") (pintype "unspecified+no_connect"))
    )
    (net (code "76") (name "unconnected-(U13-PB8-Pad45)") (class "Default")
      (node (ref "U13") (pin "45") (pinfunction "PB8_45") (pintype "unspecified+no_connect"))
    )
    (net (code "77") (name "unconnected-(U13-PB9-Pad46)") (class "Default")
      (node (ref "U13") (pin "46") (pinfunction "PB9_46") (pintype "unspecified+no_connect"))
    )
    (net (code "78") (name "unconnected-(U13-PC13-TAMPER-RTC-Pad2)") (class "Default")
      (node (ref "U13") (pin "2") (pinfunction "PC13-TAMPER-RTC_2") (pintype "unspecified+no_connect"))
    )
    (net (code "79") (name "unconnected-(U13-PC14-OSC32_IN-Pad3)") (class "Default")
      (node (ref "U13") (pin "3") (pinfunction "PC14-OSC32_IN_3") (pintype "unspecified+no_connect"))
    )
    (net (code "80") (name "unconnected-(U13-PC15-OSC32_OUT-Pad4)") (class "Default")
      (node (ref "U13") (pin "4") (pinfunction "PC15-OSC32_OUT_4") (pintype "unspecified+no_connect"))
    )
    (net (code "81") (name "unconnected-(U13-VBAT-Pad1)") (class "Default")
      (node (ref "U13") (pin "1") (pinfunction "VBAT_1") (pintype "unspecified+no_connect"))
    )
  )
)
